# v6_io_34_35_36_37_38.net
KiCad netlist of a schematic drawn in Altium Designer
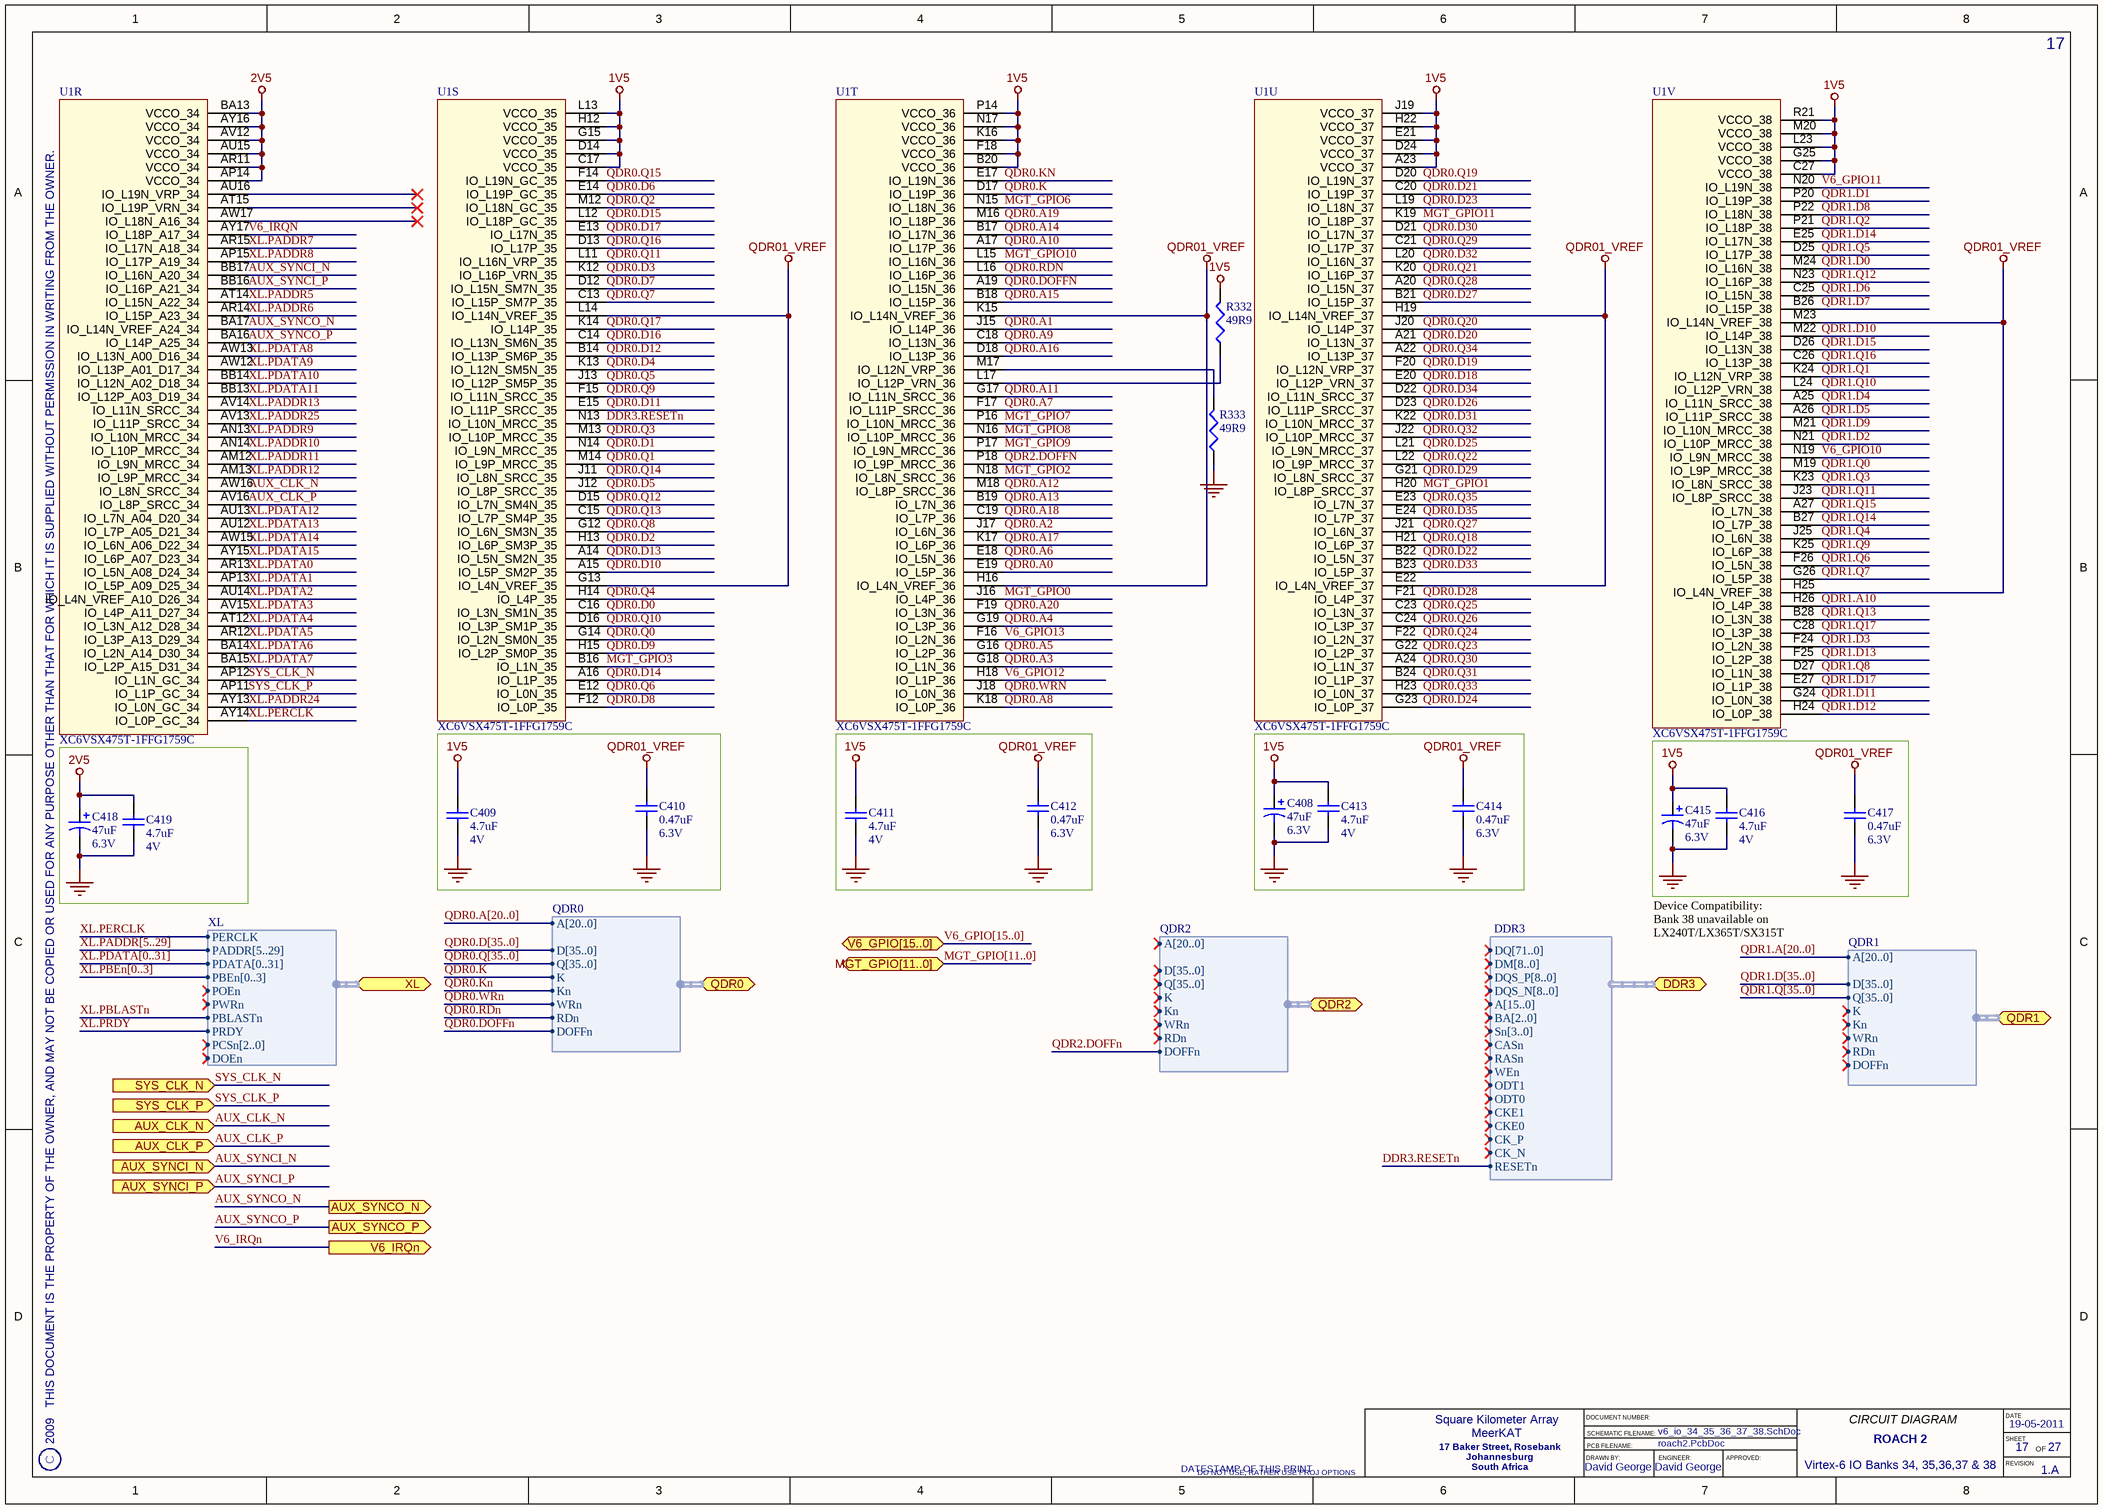
[diagram p0: v6_io_34_35_36_37_38.SchDoc]

(export (version "E")
  (design (tool "Eeschema 10.0.6"))
  (components
    (comp (ref "C408")
      (value "47uF")
      (footprint "CAPMP3528X120L")
      (description "47uF, Conductive Polymer Chip Capacitor")
      (fields
        (field (name "RATING") "6.3V")
        (field (name "MANUFACTURER") "KEMET")
        (field (name "PARTNUM") "T520T476M006ATE070")
      )
      (libsource (lib "altium_db") (part "CapPol"))
    )
    (comp (ref "C409")
      (value "4.7uF")
      (footprint "CAPC1005X60L")
      (description "4.7uF, Ceramic Capacitor")
      (fields
        (field (name "RATING") "4V")
        (field (name "MANUFACTURER") "MURATA")
        (field (name "PARTNUM") "AMK105BJ475MV-F")
      )
      (libsource (lib "altium_db") (part "CapStd"))
    )
    (comp (ref "C410")
      (value "0.47uF")
      (footprint "CAPC1005X55L")
      (description "0.47uF, Ceramic Capacitor")
      (fields
        (field (name "RATING") "6.3V")
        (field (name "MANUFACTURER") "MURATA")
        (field (name "PARTNUM") "GRM155R60J474KE19")
      )
      (libsource (lib "altium_db") (part "CapStd"))
    )
    (comp (ref "C411")
      (value "4.7uF")
      (footprint "CAPC1005X60L")
      (description "4.7uF, Ceramic Capacitor")
      (fields
        (field (name "RATING") "4V")
        (field (name "MANUFACTURER") "MURATA")
        (field (name "PARTNUM") "AMK105BJ475MV-F")
      )
      (libsource (lib "altium_db") (part "CapStd"))
    )
    (comp (ref "C412")
      (value "0.47uF")
      (footprint "CAPC1005X55L")
      (description "0.47uF, Ceramic Capacitor")
      (fields
        (field (name "RATING") "6.3V")
        (field (name "MANUFACTURER") "MURATA")
        (field (name "PARTNUM") "GRM155R60J474KE19")
      )
      (libsource (lib "altium_db") (part "CapStd"))
    )
    (comp (ref "C413")
      (value "4.7uF")
      (footprint "CAPC1005X60L")
      (description "4.7uF, Ceramic Capacitor")
      (fields
        (field (name "RATING") "4V")
        (field (name "MANUFACTURER") "MURATA")
        (field (name "PARTNUM") "AMK105BJ475MV-F")
      )
      (libsource (lib "altium_db") (part "CapStd"))
    )
    (comp (ref "C414")
      (value "0.47uF")
      (footprint "CAPC1005X55L")
      (description "0.47uF, Ceramic Capacitor")
      (fields
        (field (name "RATING") "6.3V")
        (field (name "MANUFACTURER") "MURATA")
        (field (name "PARTNUM") "GRM155R60J474KE19")
      )
      (libsource (lib "altium_db") (part "CapStd"))
    )
    (comp (ref "C415")
      (value "47uF")
      (footprint "CAPMP3528X120L")
      (description "47uF, Conductive Polymer Chip Capacitor")
      (fields
        (field (name "RATING") "6.3V")
        (field (name "MANUFACTURER") "KEMET")
        (field (name "PARTNUM") "T520T476M006ATE070")
      )
      (libsource (lib "altium_db") (part "CapPol"))
    )
    (comp (ref "C416")
      (value "4.7uF")
      (footprint "CAPC1005X60L")
      (description "4.7uF, Ceramic Capacitor")
      (fields
        (field (name "RATING") "4V")
        (field (name "MANUFACTURER") "MURATA")
        (field (name "PARTNUM") "AMK105BJ475MV-F")
      )
      (libsource (lib "altium_db") (part "CapStd"))
    )
    (comp (ref "C417")
      (value "0.47uF")
      (footprint "CAPC1005X55L")
      (description "0.47uF, Ceramic Capacitor")
      (fields
        (field (name "RATING") "6.3V")
        (field (name "MANUFACTURER") "MURATA")
        (field (name "PARTNUM") "GRM155R60J474KE19")
      )
      (libsource (lib "altium_db") (part "CapStd"))
    )
    (comp (ref "C418")
      (value "47uF")
      (footprint "CAPMP3528X120L")
      (description "47uF, Conductive Polymer Chip Capacitor")
      (fields
        (field (name "RATING") "6.3V")
        (field (name "MANUFACTURER") "KEMET")
        (field (name "PARTNUM") "T520T476M006ATE070")
      )
      (libsource (lib "altium_db") (part "CapPol"))
    )
    (comp (ref "C419")
      (value "4.7uF")
      (footprint "CAPC1005X60L")
      (description "4.7uF, Ceramic Capacitor")
      (fields
        (field (name "RATING") "4V")
        (field (name "MANUFACTURER") "MURATA")
        (field (name "PARTNUM") "AMK105BJ475MV-F")
      )
      (libsource (lib "altium_db") (part "CapStd"))
    )
    (comp (ref "R332")
      (value "49R9")
      (footprint "RESC1005X40L")
      (description "49R9, 1.1mm x 0.5mm, Thick Film Resistor")
      (fields (field (name "MANUFACTURER") "ROYALOHM") (field (name "PARTNUM") "0402WGF499JT1E"))
      (libsource (lib "altium_db") (part "ResStd"))
    )
    (comp (ref "R333")
      (value "49R9")
      (footprint "RESC1005X40L")
      (description "49R9, 1.1mm x 0.5mm, Thick Film Resistor")
      (fields (field (name "MANUFACTURER") "ROYALOHM") (field (name "PARTNUM") "0402WGF499JT1E"))
      (libsource (lib "altium_db") (part "ResStd"))
    )
    (comp (ref "U1")
      (value "XC6VSX475T-1FFG1759C")
      (footprint "FFG1759")
      (description "Virtex-6 475SXT 1760-pin FPGA")
      (fields (field (name "MANUFACTURER") "Xilinx"))
      (libsource (lib "altium_db") (part "XC6VSX475T-1FFG1759C"))
    )
  )
  (nets
    (net (code "89") (name "/AUX_CLK_N") (class "Default")
      (node (ref "U1") (pin "AW16") (pinfunction "IO_L8N_SRCC_34_AW16") (pintype "passive"))
    )
    (net (code "90") (name "/AUX_CLK_P") (class "Default")
      (node (ref "U1") (pin "AV16") (pinfunction "IO_L8P_SRCC_34_AV16") (pintype "passive"))
    )
    (net (code "91") (name "/AUX_SYNCI_N") (class "Default")
      (node (ref "U1") (pin "BB17") (pinfunction "IO_L16N_A20_34_BB17") (pintype "passive"))
    )
    (net (code "92") (name "/AUX_SYNCI_P") (class "Default")
      (node (ref "U1") (pin "BB16") (pinfunction "IO_L16P_A21_34_BB16") (pintype "passive"))
    )
    (net (code "93") (name "/AUX_SYNCO_N") (class "Default")
      (node (ref "U1") (pin "BA17") (pinfunction "IO_L14N_VREF_A24_34_BA17") (pintype "passive"))
    )
    (net (code "94") (name "/AUX_SYNCO_P") (class "Default")
      (node (ref "U1") (pin "BA16") (pinfunction "IO_L14P_A25_34_BA16") (pintype "passive"))
    )
    (net (code "95") (name "/DDR3.RESETn") (class "Default")
      (node (ref "U1") (pin "N13") (pinfunction "IO_L10N_MRCC_35_N13") (pintype "passive"))
    )
    (net (code "96") (name "/MGT_GPIO0") (class "Default")
      (node (ref "U1") (pin "J16") (pinfunction "IO_L4P_36_J16") (pintype "passive"))
    )
    (net (code "97") (name "/MGT_GPIO1") (class "Default")
      (node (ref "U1") (pin "H20") (pinfunction "IO_L8P_SRCC_37_H20") (pintype "passive"))
    )
    (net (code "98") (name "/MGT_GPIO2") (class "Default")
      (node (ref "U1") (pin "N18") (pinfunction "IO_L8N_SRCC_36_N18") (pintype "passive"))
    )
    (net (code "99") (name "/MGT_GPIO3") (class "Default")
      (node (ref "U1") (pin "B16") (pinfunction "IO_L1N_35_B16") (pintype "passive"))
    )
    (net (code "100") (name "/MGT_GPIO6") (class "Default")
      (node (ref "U1") (pin "N15") (pinfunction "IO_L18N_36_N15") (pintype "passive"))
    )
    (net (code "101") (name "/MGT_GPIO7") (class "Default")
      (node (ref "U1") (pin "P16") (pinfunction "IO_L10N_MRCC_36_P16") (pintype "passive"))
    )
    (net (code "102") (name "/MGT_GPIO8") (class "Default")
      (node (ref "U1") (pin "N16") (pinfunction "IO_L10P_MRCC_36_N16") (pintype "passive"))
    )
    (net (code "103") (name "/MGT_GPIO9") (class "Default")
      (node (ref "U1") (pin "P17") (pinfunction "IO_L9N_MRCC_36_P17") (pintype "passive"))
    )
    (net (code "104") (name "/MGT_GPIO10") (class "Default")
      (node (ref "U1") (pin "L15") (pinfunction "IO_L16N_36_L15") (pintype "passive"))
    )
    (net (code "105") (name "/MGT_GPIO11") (class "Default")
      (node (ref "U1") (pin "K19") (pinfunction "IO_L18P_37_K19") (pintype "passive"))
    )
    (net (code "107") (name "/QDR0.A0") (class "Default")
      (node (ref "U1") (pin "E19") (pinfunction "IO_L5P_36_E19") (pintype "passive"))
    )
    (net (code "108") (name "/QDR0.A1") (class "Default")
      (node (ref "U1") (pin "J15") (pinfunction "IO_L14P_36_J15") (pintype "passive"))
    )
    (net (code "109") (name "/QDR0.A2") (class "Default")
      (node (ref "U1") (pin "J17") (pinfunction "IO_L6N_36_J17") (pintype "passive"))
    )
    (net (code "110") (name "/QDR0.A3") (class "Default")
      (node (ref "U1") (pin "G18") (pinfunction "IO_L1N_36_G18") (pintype "passive"))
    )
    (net (code "111") (name "/QDR0.A4") (class "Default")
      (node (ref "U1") (pin "G19") (pinfunction "IO_L3P_36_G19") (pintype "passive"))
    )
    (net (code "112") (name "/QDR0.A5") (class "Default")
      (node (ref "U1") (pin "G16") (pinfunction "IO_L2P_36_G16") (pintype "passive"))
    )
    (net (code "113") (name "/QDR0.A6") (class "Default")
      (node (ref "U1") (pin "E18") (pinfunction "IO_L5N_36_E18") (pintype "passive"))
    )
    (net (code "114") (name "/QDR0.A7") (class "Default")
      (node (ref "U1") (pin "F17") (pinfunction "IO_L11P_SRCC_36_F17") (pintype "passive"))
    )
    (net (code "115") (name "/QDR0.A8") (class "Default")
      (node (ref "U1") (pin "K18") (pinfunction "IO_L0P_36_K18") (pintype "passive"))
    )
    (net (code "116") (name "/QDR0.A9") (class "Default")
      (node (ref "U1") (pin "C18") (pinfunction "IO_L13N_36_C18") (pintype "passive"))
    )
    (net (code "117") (name "/QDR0.A10") (class "Default")
      (node (ref "U1") (pin "A17") (pinfunction "IO_L17P_36_A17") (pintype "passive"))
    )
    (net (code "118") (name "/QDR0.A11") (class "Default")
      (node (ref "U1") (pin "G17") (pinfunction "IO_L11N_SRCC_36_G17") (pintype "passive"))
    )
    (net (code "119") (name "/QDR0.A12") (class "Default")
      (node (ref "U1") (pin "M18") (pinfunction "IO_L8P_SRCC_36_M18") (pintype "passive"))
    )
    (net (code "120") (name "/QDR0.A13") (class "Default")
      (node (ref "U1") (pin "B19") (pinfunction "IO_L7N_36_B19") (pintype "passive"))
    )
    (net (code "121") (name "/QDR0.A14") (class "Default")
      (node (ref "U1") (pin "B17") (pinfunction "IO_L17N_36_B17") (pintype "passive"))
    )
    (net (code "122") (name "/QDR0.A15") (class "Default")
      (node (ref "U1") (pin "B18") (pinfunction "IO_L15P_36_B18") (pintype "passive"))
    )
    (net (code "123") (name "/QDR0.A16") (class "Default")
      (node (ref "U1") (pin "D18") (pinfunction "IO_L13P_36_D18") (pintype "passive"))
    )
    (net (code "124") (name "/QDR0.A17") (class "Default")
      (node (ref "U1") (pin "K17") (pinfunction "IO_L6P_36_K17") (pintype "passive"))
    )
    (net (code "125") (name "/QDR0.A18") (class "Default")
      (node (ref "U1") (pin "C19") (pinfunction "IO_L7P_36_C19") (pintype "passive"))
    )
    (net (code "126") (name "/QDR0.A19") (class "Default")
      (node (ref "U1") (pin "M16") (pinfunction "IO_L18P_36_M16") (pintype "passive"))
    )
    (net (code "127") (name "/QDR0.A20") (class "Default")
      (node (ref "U1") (pin "F19") (pinfunction "IO_L3N_36_F19") (pintype "passive"))
    )
    (net (code "129") (name "/QDR0.D0") (class "Default")
      (node (ref "U1") (pin "C16") (pinfunction "IO_L3N_SM1N_35_C16") (pintype "passive"))
    )
    (net (code "130") (name "/QDR0.D1") (class "Default")
      (node (ref "U1") (pin "N14") (pinfunction "IO_L9N_MRCC_35_N14") (pintype "passive"))
    )
    (net (code "131") (name "/QDR0.D2") (class "Default")
      (node (ref "U1") (pin "H13") (pinfunction "IO_L6P_SM3P_35_H13") (pintype "passive"))
    )
    (net (code "132") (name "/QDR0.D3") (class "Default")
      (node (ref "U1") (pin "K12") (pinfunction "IO_L16P_VRN_35_K12") (pintype "passive"))
    )
    (net (code "133") (name "/QDR0.D4") (class "Default")
      (node (ref "U1") (pin "K13") (pinfunction "IO_L12N_SM5N_35_K13") (pintype "passive"))
    )
    (net (code "134") (name "/QDR0.D5") (class "Default")
      (node (ref "U1") (pin "J12") (pinfunction "IO_L8P_SRCC_35_J12") (pintype "passive"))
    )
    (net (code "135") (name "/QDR0.D6") (class "Default")
      (node (ref "U1") (pin "E14") (pinfunction "IO_L19P_GC_35_E14") (pintype "passive"))
    )
    (net (code "136") (name "/QDR0.D7") (class "Default")
      (node (ref "U1") (pin "D12") (pinfunction "IO_L15N_SM7N_35_D12") (pintype "passive"))
    )
    (net (code "137") (name "/QDR0.D8") (class "Default")
      (node (ref "U1") (pin "F12") (pinfunction "IO_L0P_35_F12") (pintype "passive"))
    )
    (net (code "138") (name "/QDR0.D9") (class "Default")
      (node (ref "U1") (pin "H15") (pinfunction "IO_L2P_SM0P_35_H15") (pintype "passive"))
    )
    (net (code "139") (name "/QDR0.D10") (class "Default")
      (node (ref "U1") (pin "A15") (pinfunction "IO_L5P_SM2P_35_A15") (pintype "passive"))
    )
    (net (code "140") (name "/QDR0.D11") (class "Default")
      (node (ref "U1") (pin "E15") (pinfunction "IO_L11P_SRCC_35_E15") (pintype "passive"))
    )
    (net (code "141") (name "/QDR0.D12") (class "Default")
      (node (ref "U1") (pin "B14") (pinfunction "IO_L13P_SM6P_35_B14") (pintype "passive"))
    )
    (net (code "142") (name "/QDR0.D13") (class "Default")
      (node (ref "U1") (pin "A14") (pinfunction "IO_L5N_SM2N_35_A14") (pintype "passive"))
    )
    (net (code "143") (name "/QDR0.D14") (class "Default")
      (node (ref "U1") (pin "A16") (pinfunction "IO_L1P_35_A16") (pintype "passive"))
    )
    (net (code "144") (name "/QDR0.D15") (class "Default")
      (node (ref "U1") (pin "L12") (pinfunction "IO_L18P_GC_35_L12") (pintype "passive"))
    )
    (net (code "145") (name "/QDR0.D16") (class "Default")
      (node (ref "U1") (pin "C14") (pinfunction "IO_L13N_SM6N_35_C14") (pintype "passive"))
    )
    (net (code "146") (name "/QDR0.D17") (class "Default")
      (node (ref "U1") (pin "E13") (pinfunction "IO_L17N_35_E13") (pintype "passive"))
    )
    (net (code "147") (name "/QDR0.D18") (class "Default")
      (node (ref "U1") (pin "E20") (pinfunction "IO_L12P_VRN_37_E20") (pintype "passive"))
    )
    (net (code "148") (name "/QDR0.D19") (class "Default")
      (node (ref "U1") (pin "F20") (pinfunction "IO_L12N_VRP_37_F20") (pintype "passive"))
    )
    (net (code "149") (name "/QDR0.D20") (class "Default")
      (node (ref "U1") (pin "A21") (pinfunction "IO_L13N_37_A21") (pintype "passive"))
    )
    (net (code "150") (name "/QDR0.D21") (class "Default")
      (node (ref "U1") (pin "C20") (pinfunction "IO_L19P_37_C20") (pintype "passive"))
    )
    (net (code "151") (name "/QDR0.D22") (class "Default")
      (node (ref "U1") (pin "B22") (pinfunction "IO_L5N_37_B22") (pintype "passive"))
    )
    (net (code "152") (name "/QDR0.D23") (class "Default")
      (node (ref "U1") (pin "L19") (pinfunction "IO_L18N_37_L19") (pintype "passive"))
    )
    (net (code "153") (name "/QDR0.D24") (class "Default")
      (node (ref "U1") (pin "G23") (pinfunction "IO_L0P_37_G23") (pintype "passive"))
    )
    (net (code "154") (name "/QDR0.D25") (class "Default")
      (node (ref "U1") (pin "L21") (pinfunction "IO_L9N_MRCC_37_L21") (pintype "passive"))
    )
    (net (code "155") (name "/QDR0.D26") (class "Default")
      (node (ref "U1") (pin "D23") (pinfunction "IO_L11P_SRCC_37_D23") (pintype "passive"))
    )
    (net (code "156") (name "/QDR0.D27") (class "Default")
      (node (ref "U1") (pin "B21") (pinfunction "IO_L15P_37_B21") (pintype "passive"))
    )
    (net (code "157") (name "/QDR0.D28") (class "Default")
      (node (ref "U1") (pin "F21") (pinfunction "IO_L4P_37_F21") (pintype "passive"))
    )
    (net (code "158") (name "/QDR0.D29") (class "Default")
      (node (ref "U1") (pin "G21") (pinfunction "IO_L8N_SRCC_37_G21") (pintype "passive"))
    )
    (net (code "159") (name "/QDR0.D30") (class "Default")
      (node (ref "U1") (pin "D21") (pinfunction "IO_L17N_37_D21") (pintype "passive"))
    )
    (net (code "160") (name "/QDR0.D31") (class "Default")
      (node (ref "U1") (pin "K22") (pinfunction "IO_L10N_MRCC_37_K22") (pintype "passive"))
    )
    (net (code "161") (name "/QDR0.D32") (class "Default")
      (node (ref "U1") (pin "L20") (pinfunction "IO_L16N_37_L20") (pintype "passive"))
    )
    (net (code "162") (name "/QDR0.D33") (class "Default")
      (node (ref "U1") (pin "B23") (pinfunction "IO_L5P_37_B23") (pintype "passive"))
    )
    (net (code "163") (name "/QDR0.D34") (class "Default")
      (node (ref "U1") (pin "D22") (pinfunction "IO_L11N_SRCC_37_D22") (pintype "passive"))
    )
    (net (code "164") (name "/QDR0.D35") (class "Default")
      (node (ref "U1") (pin "E24") (pinfunction "IO_L7P_37_E24") (pintype "passive"))
    )
    (net (code "165") (name "/QDR0.DOFFN") (class "Default")
      (node (ref "U1") (pin "A19") (pinfunction "IO_L15N_36_A19") (pintype "passive"))
    )
    (net (code "168") (name "/QDR0.K") (class "Default")
      (node (ref "U1") (pin "D17") (pinfunction "IO_L19P_36_D17") (pintype "passive"))
    )
    (net (code "169") (name "/QDR0.KN") (class "Default")
      (node (ref "U1") (pin "E17") (pinfunction "IO_L19N_36_E17") (pintype "passive"))
    )
    (net (code "171") (name "/QDR0.Q0") (class "Default")
      (node (ref "U1") (pin "G14") (pinfunction "IO_L2N_SM0N_35_G14") (pintype "passive"))
    )
    (net (code "172") (name "/QDR0.Q1") (class "Default")
      (node (ref "U1") (pin "M14") (pinfunction "IO_L9P_MRCC_35_M14") (pintype "passive"))
    )
    (net (code "173") (name "/QDR0.Q2") (class "Default")
      (node (ref "U1") (pin "M12") (pinfunction "IO_L18N_GC_35_M12") (pintype "passive"))
    )
    (net (code "174") (name "/QDR0.Q3") (class "Default")
      (node (ref "U1") (pin "M13") (pinfunction "IO_L10P_MRCC_35_M13") (pintype "passive"))
    )
    (net (code "175") (name "/QDR0.Q4") (class "Default")
      (node (ref "U1") (pin "H14") (pinfunction "IO_L4P_35_H14") (pintype "passive"))
    )
    (net (code "176") (name "/QDR0.Q5") (class "Default")
      (node (ref "U1") (pin "J13") (pinfunction "IO_L12P_SM5P_35_J13") (pintype "passive"))
    )
    (net (code "177") (name "/QDR0.Q6") (class "Default")
      (node (ref "U1") (pin "E12") (pinfunction "IO_L0N_35_E12") (pintype "passive"))
    )
    (net (code "178") (name "/QDR0.Q7") (class "Default")
      (node (ref "U1") (pin "C13") (pinfunction "IO_L15P_SM7P_35_C13") (pintype "passive"))
    )
    (net (code "179") (name "/QDR0.Q8") (class "Default")
      (node (ref "U1") (pin "G12") (pinfunction "IO_L6N_SM3N_35_G12") (pintype "passive"))
    )
    (net (code "180") (name "/QDR0.Q9") (class "Default")
      (node (ref "U1") (pin "F15") (pinfunction "IO_L11N_SRCC_35_F15") (pintype "passive"))
    )
    (net (code "181") (name "/QDR0.Q10") (class "Default")
      (node (ref "U1") (pin "D16") (pinfunction "IO_L3P_SM1P_35_D16") (pintype "passive"))
    )
    (net (code "182") (name "/QDR0.Q11") (class "Default")
      (node (ref "U1") (pin "L11") (pinfunction "IO_L16N_VRP_35_L11") (pintype "passive"))
    )
    (net (code "183") (name "/QDR0.Q12") (class "Default")
      (node (ref "U1") (pin "D15") (pinfunction "IO_L7N_SM4N_35_D15") (pintype "passive"))
    )
    (net (code "184") (name "/QDR0.Q13") (class "Default")
      (node (ref "U1") (pin "C15") (pinfunction "IO_L7P_SM4P_35_C15") (pintype "passive"))
    )
    (net (code "185") (name "/QDR0.Q14") (class "Default")
      (node (ref "U1") (pin "J11") (pinfunction "IO_L8N_SRCC_35_J11") (pintype "passive"))
    )
    (net (code "186") (name "/QDR0.Q15") (class "Default")
      (node (ref "U1") (pin "F14") (pinfunction "IO_L19N_GC_35_F14") (pintype "passive"))
    )
    (net (code "187") (name "/QDR0.Q16") (class "Default")
      (node (ref "U1") (pin "D13") (pinfunction "IO_L17P_35_D13") (pintype "passive"))
    )
    (net (code "188") (name "/QDR0.Q17") (class "Default")
      (node (ref "U1") (pin "K14") (pinfunction "IO_L14P_35_K14") (pintype "passive"))
    )
    (net (code "189") (name "/QDR0.Q18") (class "Default")
      (node (ref "U1") (pin "H21") (pinfunction "IO_L6P_37_H21") (pintype "passive"))
    )
    (net (code "190") (name "/QDR0.Q19") (class "Default")
      (node (ref "U1") (pin "D20") (pinfunction "IO_L19N_37_D20") (pintype "passive"))
    )
    (net (code "191") (name "/QDR0.Q20") (class "Default")
      (node (ref "U1") (pin "J20") (pinfunction "IO_L14P_37_J20") (pintype "passive"))
    )
    (net (code "192") (name "/QDR0.Q21") (class "Default")
      (node (ref "U1") (pin "K20") (pinfunction "IO_L16P_37_K20") (pintype "passive"))
    )
    (net (code "193") (name "/QDR0.Q22") (class "Default")
      (node (ref "U1") (pin "L22") (pinfunction "IO_L9P_MRCC_37_L22") (pintype "passive"))
    )
    (net (code "194") (name "/QDR0.Q23") (class "Default")
      (node (ref "U1") (pin "G22") (pinfunction "IO_L2P_37_G22") (pintype "passive"))
    )
    (net (code "195") (name "/QDR0.Q24") (class "Default")
      (node (ref "U1") (pin "F22") (pinfunction "IO_L2N_37_F22") (pintype "passive"))
    )
    (net (code "196") (name "/QDR0.Q25") (class "Default")
      (node (ref "U1") (pin "C23") (pinfunction "IO_L3N_37_C23") (pintype "passive"))
    )
    (net (code "197") (name "/QDR0.Q26") (class "Default")
      (node (ref "U1") (pin "C24") (pinfunction "IO_L3P_37_C24") (pintype "passive"))
    )
    (net (code "198") (name "/QDR0.Q27") (class "Default")
      (node (ref "U1") (pin "J21") (pinfunction "IO_L6N_37_J21") (pintype "passive"))
    )
    (net (code "199") (name "/QDR0.Q28") (class "Default")
      (node (ref "U1") (pin "A20") (pinfunction "IO_L15N_37_A20") (pintype "passive"))
    )
    (net (code "200") (name "/QDR0.Q29") (class "Default")
      (node (ref "U1") (pin "C21") (pinfunction "IO_L17P_37_C21") (pintype "passive"))
    )
    (net (code "201") (name "/QDR0.Q30") (class "Default")
      (node (ref "U1") (pin "A24") (pinfunction "IO_L1N_37_A24") (pintype "passive"))
    )
    (net (code "202") (name "/QDR0.Q31") (class "Default")
      (node (ref "U1") (pin "B24") (pinfunction "IO_L1P_37_B24") (pintype "passive"))
    )
    (net (code "203") (name "/QDR0.Q32") (class "Default")
      (node (ref "U1") (pin "J22") (pinfunction "IO_L10P_MRCC_37_J22") (pintype "passive"))
    )
    (net (code "204") (name "/QDR0.Q33") (class "Default")
      (node (ref "U1") (pin "H23") (pinfunction "IO_L0N_37_H23") (pintype "passive"))
    )
    (net (code "205") (name "/QDR0.Q34") (class "Default")
      (node (ref "U1") (pin "A22") (pinfunction "IO_L13P_37_A22") (pintype "passive"))
    )
    (net (code "206") (name "/QDR0.Q35") (class "Default")
      (node (ref "U1") (pin "E23") (pinfunction "IO_L7N_37_E23") (pintype "passive"))
    )
    (net (code "207") (name "/QDR0.RDN") (class "Default")
      (node (ref "U1") (pin "L16") (pinfunction "IO_L16P_36_L16") (pintype "passive"))
    )
    (net (code "209") (name "/QDR0.WRN") (class "Default")
      (node (ref "U1") (pin "J18") (pinfunction "IO_L0N_36_J18") (pintype "passive"))
    )
    (net (code "212") (name "/QDR1.A10") (class "Default")
      (node (ref "U1") (pin "H26") (pinfunction "IO_L4P_38_H26") (pintype "passive"))
    )
    (net (code "214") (name "/QDR1.D0") (class "Default")
      (node (ref "U1") (pin "M24") (pinfunction "IO_L16N_38_M24") (pintype "passive"))
    )
    (net (code "215") (name "/QDR1.D1") (class "Default")
      (node (ref "U1") (pin "P20") (pinfunction "IO_L19P_38_P20") (pintype "passive"))
    )
    (net (code "216") (name "/QDR1.D2") (class "Default")
      (node (ref "U1") (pin "N21") (pinfunction "IO_L10P_MRCC_38_N21") (pintype "passive"))
    )
    (net (code "217") (name "/QDR1.D3") (class "Default")
      (node (ref "U1") (pin "F24") (pinfunction "IO_L2N_38_F24") (pintype "passive"))
    )
    (net (code "218") (name "/QDR1.D4") (class "Default")
      (node (ref "U1") (pin "A25") (pinfunction "IO_L11N_SRCC_38_A25") (pintype "passive"))
    )
    (net (code "219") (name "/QDR1.D5") (class "Default")
      (node (ref "U1") (pin "A26") (pinfunction "IO_L11P_SRCC_38_A26") (pintype "passive"))
    )
    (net (code "220") (name "/QDR1.D6") (class "Default")
      (node (ref "U1") (pin "C25") (pinfunction "IO_L15N_38_C25") (pintype "passive"))
    )
    (net (code "221") (name "/QDR1.D7") (class "Default")
      (node (ref "U1") (pin "B26") (pinfunction "IO_L15P_38_B26") (pintype "passive"))
    )
    (net (code "222") (name "/QDR1.D8") (class "Default")
      (node (ref "U1") (pin "P22") (pinfunction "IO_L18N_38_P22") (pintype "passive"))
    )
    (net (code "223") (name "/QDR1.D9") (class "Default")
      (node (ref "U1") (pin "M21") (pinfunction "IO_L10N_MRCC_38_M21") (pintype "passive"))
    )
    (net (code "224") (name "/QDR1.D10") (class "Default")
      (node (ref "U1") (pin "M22") (pinfunction "IO_L14P_38_M22") (pintype "passive"))
    )
    (net (code "225") (name "/QDR1.D11") (class "Default")
      (node (ref "U1") (pin "G24") (pinfunction "IO_L0N_38_G24") (pintype "passive"))
    )
    (net (code "226") (name "/QDR1.D12") (class "Default")
      (node (ref "U1") (pin "H24") (pinfunction "IO_L0P_38_H24") (pintype "passive"))
    )
    (net (code "227") (name "/QDR1.D13") (class "Default")
      (node (ref "U1") (pin "F25") (pinfunction "IO_L2P_38_F25") (pintype "passive"))
    )
    (net (code "228") (name "/QDR1.D14") (class "Default")
      (node (ref "U1") (pin "E25") (pinfunction "IO_L17N_38_E25") (pintype "passive"))
    )
    (net (code "229") (name "/QDR1.D15") (class "Default")
      (node (ref "U1") (pin "D26") (pinfunction "IO_L13N_38_D26") (pintype "passive"))
    )
    (net (code "230") (name "/QDR1.D17") (class "Default")
      (node (ref "U1") (pin "E27") (pinfunction "IO_L1P_38_E27") (pintype "passive"))
    )
    (net (code "232") (name "/QDR1.Q0") (class "Default")
      (node (ref "U1") (pin "M19") (pinfunction "IO_L9P_MRCC_38_M19") (pintype "passive"))
    )
    (net (code "233") (name "/QDR1.Q1") (class "Default")
      (node (ref "U1") (pin "K24") (pinfunction "IO_L12N_VRP_38_K24") (pintype "passive"))
    )
    (net (code "234") (name "/QDR1.Q2") (class "Default")
      (node (ref "U1") (pin "P21") (pinfunction "IO_L18P_38_P21") (pintype "passive"))
    )
    (net (code "235") (name "/QDR1.Q3") (class "Default")
      (node (ref "U1") (pin "K23") (pinfunction "IO_L8N_SRCC_38_K23") (pintype "passive"))
    )
    (net (code "236") (name "/QDR1.Q4") (class "Default")
      (node (ref "U1") (pin "J25") (pinfunction "IO_L6N_38_J25") (pintype "passive"))
    )
    (net (code "237") (name "/QDR1.Q5") (class "Default")
      (node (ref "U1") (pin "D25") (pinfunction "IO_L17P_38_D25") (pintype "passive"))
    )
    (net (code "238") (name "/QDR1.Q6") (class "Default")
      (node (ref "U1") (pin "F26") (pinfunction "IO_L5N_38_F26") (pintype "passive"))
    )
    (net (code "239") (name "/QDR1.Q7") (class "Default")
      (node (ref "U1") (pin "G26") (pinfunction "IO_L5P_38_G26") (pintype "passive"))
    )
    (net (code "240") (name "/QDR1.Q8") (class "Default")
      (node (ref "U1") (pin "D27") (pinfunction "IO_L1N_38_D27") (pintype "passive"))
    )
    (net (code "241") (name "/QDR1.Q9") (class "Default")
      (node (ref "U1") (pin "K25") (pinfunction "IO_L6P_38_K25") (pintype "passive"))
    )
    (net (code "242") (name "/QDR1.Q10") (class "Default")
      (node (ref "U1") (pin "L24") (pinfunction "IO_L12P_VRN_38_L24") (pintype "passive"))
    )
    (net (code "243") (name "/QDR1.Q11") (class "Default")
      (node (ref "U1") (pin "J23") (pinfunction "IO_L8P_SRCC_38_J23") (pintype "passive"))
    )
    (net (code "244") (name "/QDR1.Q12") (class "Default")
      (node (ref "U1") (pin "N23") (pinfunction "IO_L16P_38_N23") (pintype "passive"))
    )
    (net (code "245") (name "/QDR1.Q13") (class "Default")
      (node (ref "U1") (pin "B28") (pinfunction "IO_L3N_38_B28") (pintype "passive"))
    )
    (net (code "246") (name "/QDR1.Q14") (class "Default")
      (node (ref "U1") (pin "B27") (pinfunction "IO_L7P_38_B27") (pintype "passive"))
    )
    (net (code "247") (name "/QDR1.Q15") (class "Default")
      (node (ref "U1") (pin "A27") (pinfunction "IO_L7N_38_A27") (pintype "passive"))
    )
    (net (code "248") (name "/QDR1.Q16") (class "Default")
      (node (ref "U1") (pin "C26") (pinfunction "IO_L13P_38_C26") (pintype "passive"))
    )
    (net (code "249") (name "/QDR1.Q17") (class "Default")
      (node (ref "U1") (pin "C28") (pinfunction "IO_L3P_38_C28") (pintype "passive"))
    )
    (net (code "251") (name "/QDR2.DOFFN") (class "Default")
      (node (ref "U1") (pin "P18") (pinfunction "IO_L9P_MRCC_36_P18") (pintype "passive"))
    )
    (net (code "253") (name "/SYS_CLK_N") (class "Default")
      (node (ref "U1") (pin "AP12") (pinfunction "IO_L1N_GC_34_AP12") (pintype "passive"))
    )
    (net (code "254") (name "/SYS_CLK_P") (class "Default")
      (node (ref "U1") (pin "AP11") (pinfunction "IO_L1P_GC_34_AP11") (pintype "passive"))
    )
    (net (code "255") (name "/V6_GPIO10") (class "Default")
      (node (ref "U1") (pin "N19") (pinfunction "IO_L9N_MRCC_38_N19") (pintype "passive"))
    )
    (net (code "256") (name "/V6_GPIO11") (class "Default")
      (node (ref "U1") (pin "N20") (pinfunction "IO_L19N_38_N20") (pintype "passive"))
    )
    (net (code "257") (name "/V6_GPIO12") (class "Default")
      (node (ref "U1") (pin "H18") (pinfunction "IO_L1P_36_H18") (pintype "passive"))
    )
    (net (code "258") (name "/V6_GPIO13") (class "Default")
      (node (ref "U1") (pin "F16") (pinfunction "IO_L2N_36_F16") (pintype "passive"))
    )
    (net (code "260") (name "/V6_IRQN") (class "Default")
      (node (ref "U1") (pin "AY17") (pinfunction "IO_L18P_A17_34_AY17") (pintype "passive"))
    )
    (net (code "262") (name "/XL.PADDR5") (class "Default")
      (node (ref "U1") (pin "AT14") (pinfunction "IO_L15N_A22_34_AT14") (pintype "passive"))
    )
    (net (code "263") (name "/XL.PADDR6") (class "Default")
      (node (ref "U1") (pin "AR14") (pinfunction "IO_L15P_A23_34_AR14") (pintype "passive"))
    )
    (net (code "264") (name "/XL.PADDR7") (class "Default")
      (node (ref "U1") (pin "AR15") (pinfunction "IO_L17N_A18_34_AR15") (pintype "passive"))
    )
    (net (code "265") (name "/XL.PADDR8") (class "Default")
      (node (ref "U1") (pin "AP15") (pinfunction "IO_L17P_A19_34_AP15") (pintype "passive"))
    )
    (net (code "266") (name "/XL.PADDR9") (class "Default")
      (node (ref "U1") (pin "AN13") (pinfunction "IO_L10N_MRCC_34_AN13") (pintype "passive"))
    )
    (net (code "267") (name "/XL.PADDR10") (class "Default")
      (node (ref "U1") (pin "AN14") (pinfunction "IO_L10P_MRCC_34_AN14") (pintype "passive"))
    )
    (net (code "268") (name "/XL.PADDR11") (class "Default")
      (node (ref "U1") (pin "AM12") (pinfunction "IO_L9N_MRCC_34_AM12") (pintype "passive"))
    )
    (net (code "269") (name "/XL.PADDR12") (class "Default")
      (node (ref "U1") (pin "AM13") (pinfunction "IO_L9P_MRCC_34_AM13") (pintype "passive"))
    )
    (net (code "270") (name "/XL.PADDR13") (class "Default")
      (node (ref "U1") (pin "AV14") (pinfunction "IO_L11N_SRCC_34_AV14") (pintype "passive"))
    )
    (net (code "271") (name "/XL.PADDR24") (class "Default")
      (node (ref "U1") (pin "AY13") (pinfunction "IO_L0N_GC_34_AY13") (pintype "passive"))
    )
    (net (code "272") (name "/XL.PADDR25") (class "Default")
      (node (ref "U1") (pin "AV13") (pinfunction "IO_L11P_SRCC_34_AV13") (pintype "passive"))
    )
    (net (code "275") (name "/XL.PDATA0") (class "Default")
      (node (ref "U1") (pin "AR13") (pinfunction "IO_L5N_A08_D24_34_AR13") (pintype "passive"))
    )
    (net (code "276") (name "/XL.PDATA1") (class "Default")
      (node (ref "U1") (pin "AP13") (pinfunction "IO_L5P_A09_D25_34_AP13") (pintype "passive"))
    )
    (net (code "277") (name "/XL.PDATA2") (class "Default")
      (node (ref "U1") (pin "AU14") (pinfunction "IO_L4N_VREF_A10_D26_34_AU14") (pintype "passive"))
    )
    (net (code "278") (name "/XL.PDATA3") (class "Default")
      (node (ref "U1") (pin "AV15") (pinfunction "IO_L4P_A11_D27_34_AV15") (pintype "passive"))
    )
    (net (code "279") (name "/XL.PDATA4") (class "Default")
      (node (ref "U1") (pin "AT12") (pinfunction "IO_L3N_A12_D28_34_AT12") (pintype "passive"))
    )
    (net (code "280") (name "/XL.PDATA5") (class "Default")
      (node (ref "U1") (pin "AR12") (pinfunction "IO_L3P_A13_D29_34_AR12") (pintype "passive"))
    )
    (net (code "281") (name "/XL.PDATA6") (class "Default")
      (node (ref "U1") (pin "BA14") (pinfunction "IO_L2N_A14_D30_34_BA14") (pintype "passive"))
    )
    (net (code "282") (name "/XL.PDATA7") (class "Default")
      (node (ref "U1") (pin "BA15") (pinfunction "IO_L2P_A15_D31_34_BA15") (pintype "passive"))
    )
    (net (code "283") (name "/XL.PDATA8") (class "Default")
      (node (ref "U1") (pin "AW13") (pinfunction "IO_L13N_A00_D16_34_AW13") (pintype "passive"))
    )
    (net (code "284") (name "/XL.PDATA9") (class "Default")
      (node (ref "U1") (pin "AW12") (pinfunction "IO_L13P_A01_D17_34_AW12") (pintype "passive"))
    )
    (net (code "285") (name "/XL.PDATA10") (class "Default")
      (node (ref "U1") (pin "BB14") (pinfunction "IO_L12N_A02_D18_34_BB14") (pintype "passive"))
    )
    (net (code "286") (name "/XL.PDATA11") (class "Default")
      (node (ref "U1") (pin "BB13") (pinfunction "IO_L12P_A03_D19_34_BB13") (pintype "passive"))
    )
    (net (code "287") (name "/XL.PDATA12") (class "Default")
      (node (ref "U1") (pin "AU13") (pinfunction "IO_L7N_A04_D20_34_AU13") (pintype "passive"))
    )
    (net (code "288") (name "/XL.PDATA13") (class "Default")
      (node (ref "U1") (pin "AU12") (pinfunction "IO_L7P_A05_D21_34_AU12") (pintype "passive"))
    )
    (net (code "289") (name "/XL.PDATA14") (class "Default")
      (node (ref "U1") (pin "AW15") (pinfunction "IO_L6N_A06_D22_34_AW15") (pintype "passive"))
    )
    (net (code "290") (name "/XL.PDATA15") (class "Default")
      (node (ref "U1") (pin "AY15") (pinfunction "IO_L6P_A07_D23_34_AY15") (pintype "passive"))
    )
    (net (code "292") (name "/XL.PERCLK") (class "Default")
      (node (ref "U1") (pin "AY14") (pinfunction "IO_L0P_GC_34_AY14") (pintype "passive"))
    )
    (net (code "300") (name "1V5") (class "Default")
      (node (ref "C408") (pin "1") (pinfunction "1_1") (pintype "passive"))
      (node (ref "C409") (pin "2") (pinfunction "2_2") (pintype "passive"))
      (node (ref "C411") (pin "2") (pinfunction "2_2") (pintype "passive"))
      (node (ref "C413") (pin "2") (pinfunction "2_2") (pintype "passive"))
      (node (ref "C415") (pin "1") (pinfunction "1_1") (pintype "passive"))
      (node (ref "C416") (pin "2") (pinfunction "2_2") (pintype "passive"))
      (node (ref "R332") (pin "2") (pinfunction "2_2") (pintype "passive"))
      (node (ref "U1") (pin "A23") (pinfunction "VCCO_37_A23") (pintype "passive"))
      (node (ref "U1") (pin "B20") (pinfunction "VCCO_36_B20") (pintype "passive"))
      (node (ref "U1") (pin "C17") (pinfunction "VCCO_35_C17") (pintype "passive"))
      (node (ref "U1") (pin "C27") (pinfunction "VCCO_38_C27") (pintype "passive"))
      (node (ref "U1") (pin "D14") (pinfunction "VCCO_35_D14") (pintype "passive"))
      (node (ref "U1") (pin "D24") (pinfunction "VCCO_37_D24") (pintype "passive"))
      (node (ref "U1") (pin "E21") (pinfunction "VCCO_37_E21") (pintype "passive"))
      (node (ref "U1") (pin "F18") (pinfunction "VCCO_36_F18") (pintype "passive"))
      (node (ref "U1") (pin "G15") (pinfunction "VCCO_35_G15") (pintype "passive"))
      (node (ref "U1") (pin "G25") (pinfunction "VCCO_38_G25") (pintype "passive"))
      (node (ref "U1") (pin "H12") (pinfunction "VCCO_35_H12") (pintype "passive"))
      (node (ref "U1") (pin "H22") (pinfunction "VCCO_37_H22") (pintype "passive"))
      (node (ref "U1") (pin "J19") (pinfunction "VCCO_37_J19") (pintype "passive"))
      (node (ref "U1") (pin "K16") (pinfunction "VCCO_36_K16") (pintype "passive"))
      (node (ref "U1") (pin "L13") (pinfunction "VCCO_35_L13") (pintype "passive"))
      (node (ref "U1") (pin "L23") (pinfunction "VCCO_38_L23") (pintype "passive"))
      (node (ref "U1") (pin "M20") (pinfunction "VCCO_38_M20") (pintype "passive"))
      (node (ref "U1") (pin "N17") (pinfunction "VCCO_36_N17") (pintype "passive"))
      (node (ref "U1") (pin "P14") (pinfunction "VCCO_36_P14") (pintype "passive"))
      (node (ref "U1") (pin "R21") (pinfunction "VCCO_38_R21") (pintype "passive"))
    )
    (net (code "301") (name "2V5") (class "Default")
      (node (ref "C418") (pin "1") (pinfunction "1_1") (pintype "passive"))
      (node (ref "C419") (pin "2") (pinfunction "2_2") (pintype "passive"))
      (node (ref "U1") (pin "AP14") (pinfunction "VCCO_34_AP14") (pintype "passive"))
      (node (ref "U1") (pin "AR11") (pinfunction "VCCO_34_AR11") (pintype "passive"))
      (node (ref "U1") (pin "AU15") (pinfunction "VCCO_34_AU15") (pintype "passive"))
      (node (ref "U1") (pin "AV12") (pinfunction "VCCO_34_AV12") (pintype "passive"))
      (node (ref "U1") (pin "AY16") (pinfunction "VCCO_34_AY16") (pintype "passive"))
      (node (ref "U1") (pin "BA13") (pinfunction "VCCO_34_BA13") (pintype "passive"))
    )
    (net (code "302") (name "GND") (class "Default")
      (node (ref "C408") (pin "2") (pinfunction "2_2") (pintype "passive"))
      (node (ref "C409") (pin "1") (pinfunction "1_1") (pintype "passive"))
      (node (ref "C410") (pin "1") (pinfunction "1_1") (pintype "passive"))
      (node (ref "C411") (pin "1") (pinfunction "1_1") (pintype "passive"))
      (node (ref "C412") (pin "1") (pinfunction "1_1") (pintype "passive"))
      (node (ref "C413") (pin "1") (pinfunction "1_1") (pintype "passive"))
      (node (ref "C414") (pin "1") (pinfunction "1_1") (pintype "passive"))
      (node (ref "C415") (pin "2") (pinfunction "2_2") (pintype "passive"))
      (node (ref "C416") (pin "1") (pinfunction "1_1") (pintype "passive"))
      (node (ref "C417") (pin "1") (pinfunction "1_1") (pintype "passive"))
      (node (ref "C418") (pin "2") (pinfunction "2_2") (pintype "passive"))
      (node (ref "C419") (pin "1") (pinfunction "1_1") (pintype "passive"))
      (node (ref "R333") (pin "1") (pinfunction "1_1") (pintype "passive"))
    )
    (net (code "303") (name "Net-(U1T-IO_L12N_VRP_36)") (class "Default")
      (node (ref "R333") (pin "2") (pinfunction "2_2") (pintype "passive"))
      (node (ref "U1") (pin "M17") (pinfunction "IO_L12N_VRP_36_M17") (pintype "passive"))
    )
    (net (code "304") (name "Net-(U1T-IO_L12P_VRN_36)") (class "Default")
      (node (ref "R332") (pin "1") (pinfunction "1_1") (pintype "passive"))
      (node (ref "U1") (pin "L17") (pinfunction "IO_L12P_VRN_36_L17") (pintype "passive"))
    )
    (net (code "305") (name "QDR01_VREF") (class "Default")
      (node (ref "C410") (pin "2") (pinfunction "2_2") (pintype "passive"))
      (node (ref "C412") (pin "2") (pinfunction "2_2") (pintype "passive"))
      (node (ref "C414") (pin "2") (pinfunction "2_2") (pintype "passive"))
      (node (ref "C417") (pin "2") (pinfunction "2_2") (pintype "passive"))
      (node (ref "U1") (pin "E22") (pinfunction "IO_L4N_VREF_37_E22") (pintype "passive"))
      (node (ref "U1") (pin "G13") (pinfunction "IO_L4N_VREF_35_G13") (pintype "passive"))
      (node (ref "U1") (pin "H16") (pinfunction "IO_L4N_VREF_36_H16") (pintype "passive"))
      (node (ref "U1") (pin "H19") (pinfunction "IO_L14N_VREF_37_H19") (pintype "passive"))
      (node (ref "U1") (pin "H25") (pinfunction "IO_L4N_VREF_38_H25") (pintype "passive"))
      (node (ref "U1") (pin "K15") (pinfunction "IO_L14N_VREF_36_K15") (pintype "passive"))
      (node (ref "U1") (pin "L14") (pinfunction "IO_L14N_VREF_35_L14") (pintype "passive"))
      (node (ref "U1") (pin "M23") (pinfunction "IO_L14N_VREF_38_M23") (pintype "passive"))
    )
    (net (code "306") (name "unconnected-(U1R-IO_L18N_A16_34-PadAW17)") (class "Default")
      (node (ref "U1") (pin "AW17") (pinfunction "IO_L18N_A16_34_AW17") (pintype "passive+no_connect"))
    )
    (net (code "307") (name "unconnected-(U1R-IO_L19N_VRP_34-PadAU16)") (class "Default")
      (node (ref "U1") (pin "AU16") (pinfunction "IO_L19N_VRP_34_AU16") (pintype "passive+no_connect"))
    )
    (net (code "308") (name "unconnected-(U1R-IO_L19P_VRN_34-PadAT15)") (class "Default")
      (node (ref "U1") (pin "AT15") (pinfunction "IO_L19P_VRN_34_AT15") (pintype "passive+no_connect"))
    )
  )
)
